# Placa_SecadorDeGraos_SL.net
KiCad netlist of a schematic drawn in EAGLE
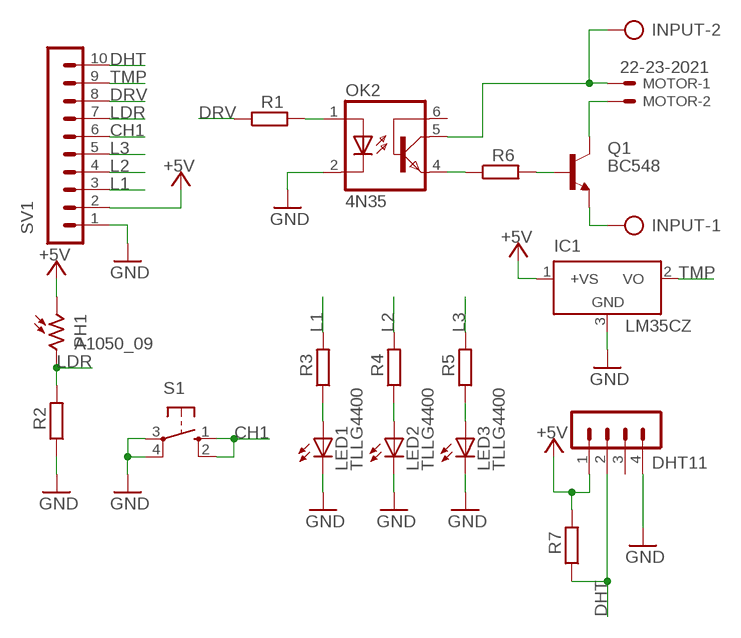
[diagram p0: schematic, sheet 1]

(export (version "E")
  (design (tool "Eeschema 10.0.6"))
  (components
    (comp (ref "DHT11")
      (value "MA04-1")
      (footprint "eagle-import:MA04-1")
      (libsource (lib "eagle-import") (part "MA04-1"))
    )
    (comp (ref "IC1")
      (value "LM35CZ")
      (footprint "eagle-import:TO92")
      (libsource (lib "eagle-import") (part "LM35CZ"))
    )
    (comp (ref "INPUT")
      (value "AK500/2")
      (footprint "eagle-import:AK500_2")
      (libsource (lib "eagle-import") (part "AK500/2"))
    )
    (comp (ref "LED1")
      (value "TLLG4400")
      (footprint "eagle-import:LED3MM")
      (fields (field (name "MF") "VISHAY SEMICONDUCTOR"))
      (libsource (lib "eagle-import") (part "TLLG4400"))
    )
    (comp (ref "LED2")
      (value "TLLG4400")
      (footprint "eagle-import:LED3MM")
      (fields (field (name "MF") "VISHAY SEMICONDUCTOR"))
      (libsource (lib "eagle-import") (part "TLLG4400"))
    )
    (comp (ref "LED3")
      (value "TLLG4400")
      (footprint "eagle-import:LED3MM")
      (fields (field (name "MF") "VISHAY SEMICONDUCTOR"))
      (libsource (lib "eagle-import") (part "TLLG4400"))
    )
    (comp (ref "MOTOR")
      (value "22-23-2021")
      (footprint "eagle-import:22-23-2021")
      (fields (field (name "MF") "MOLEX"))
      (libsource (lib "eagle-import") (part "22-23-2021"))
    )
    (comp (ref "OK2")
      (value "4N35")
      (footprint "eagle-import:DIL06")
      (fields (field (name "MF") "FAIRCHILD SEMICONDUCTOR"))
      (libsource (lib "eagle-import") (part "4N35"))
    )
    (comp (ref "PH1")
      (value "A1050_09")
      (footprint "eagle-import:T0-46-A10XX")
      (libsource (lib "eagle-import") (part "A1050_09"))
    )
    (comp (ref "Q1")
      (value "BC548")
      (footprint "eagle-import:TO92-EBC")
      (libsource (lib "eagle-import") (part "BC548"))
    )
    (comp (ref "R1")
      (value "R-EU_0204/7")
      (footprint "eagle-import:0204_7")
      (libsource (lib "eagle-import") (part "R-EU_0204/7"))
    )
    (comp (ref "R2")
      (value "R-EU_0204/7")
      (footprint "eagle-import:0204_7")
      (libsource (lib "eagle-import") (part "R-EU_0204/7"))
    )
    (comp (ref "R3")
      (value "R-EU_0204/7")
      (footprint "eagle-import:0204_7")
      (libsource (lib "eagle-import") (part "R-EU_0204/7"))
    )
    (comp (ref "R4")
      (value "R-EU_0204/7")
      (footprint "eagle-import:0204_7")
      (libsource (lib "eagle-import") (part "R-EU_0204/7"))
    )
    (comp (ref "R5")
      (value "R-EU_0204/7")
      (footprint "eagle-import:0204_7")
      (libsource (lib "eagle-import") (part "R-EU_0204/7"))
    )
    (comp (ref "R6")
      (value "R-EU_0204/7")
      (footprint "eagle-import:0204_7")
      (libsource (lib "eagle-import") (part "R-EU_0204/7"))
    )
    (comp (ref "R7")
      (value "R-EU_0204/7")
      (footprint "eagle-import:0204_7")
      (libsource (lib "eagle-import") (part "R-EU_0204/7"))
    )
    (comp (ref "S1")
      (value "10-XX")
      (footprint "eagle-import:B3F-10XX")
      (fields (field (name "MPN") "B3F-1000"))
      (libsource (lib "eagle-import") (part "10-XX"))
    )
    (comp (ref "SV1")
      (value "MA10-1")
      (footprint "eagle-import:MA10-1")
      (libsource (lib "eagle-import") (part "MA10-1"))
    )
  )
  (nets
    (net (code "1") (name "+5V") (class "Default")
      (node (ref "DHT11") (pin "1") (pinfunction "1_1") (pintype "passive"))
      (node (ref "IC1") (pin "1") (pinfunction "+VS_1") (pintype "input"))
      (node (ref "PH1") (pin "1") (pinfunction "1_1") (pintype "passive"))
      (node (ref "R7") (pin "2") (pinfunction "2_2") (pintype "passive"))
      (node (ref "SV1") (pin "2") (pinfunction "2_2") (pintype "passive"))
    )
    (net (code "2") (name "/CH1") (class "Default")
      (node (ref "S1") (pin "1") (pinfunction "S_1") (pintype "passive"))
      (node (ref "S1") (pin "2") (pinfunction "S1_2") (pintype "passive"))
      (node (ref "SV1") (pin "6") (pinfunction "6_6") (pintype "passive"))
    )
    (net (code "3") (name "/DHT") (class "Default")
      (node (ref "DHT11") (pin "2") (pinfunction "2_2") (pintype "passive"))
      (node (ref "R7") (pin "1") (pinfunction "1_1") (pintype "passive"))
      (node (ref "SV1") (pin "10") (pinfunction "10_10") (pintype "passive"))
    )
    (net (code "4") (name "/DRV") (class "Default")
      (node (ref "R1") (pin "1") (pinfunction "1_1") (pintype "passive"))
      (node (ref "SV1") (pin "8") (pinfunction "8_8") (pintype "passive"))
    )
    (net (code "5") (name "/L1") (class "Default")
      (node (ref "R3") (pin "2") (pinfunction "2_2") (pintype "passive"))
      (node (ref "SV1") (pin "3") (pinfunction "3_3") (pintype "passive"))
    )
    (net (code "6") (name "/L2") (class "Default")
      (node (ref "R4") (pin "2") (pinfunction "2_2") (pintype "passive"))
      (node (ref "SV1") (pin "4") (pinfunction "4_4") (pintype "passive"))
    )
    (net (code "7") (name "/L3") (class "Default")
      (node (ref "R5") (pin "2") (pinfunction "2_2") (pintype "passive"))
      (node (ref "SV1") (pin "5") (pinfunction "5_5") (pintype "passive"))
    )
    (net (code "8") (name "/LDR") (class "Default")
      (node (ref "PH1") (pin "2") (pinfunction "2_2") (pintype "passive"))
      (node (ref "R2") (pin "2") (pinfunction "2_2") (pintype "passive"))
      (node (ref "SV1") (pin "7") (pinfunction "7_7") (pintype "passive"))
    )
    (net (code "9") (name "/TMP") (class "Default")
      (node (ref "IC1") (pin "2") (pinfunction "VO_2") (pintype "input"))
      (node (ref "SV1") (pin "9") (pinfunction "9_9") (pintype "passive"))
    )
    (net (code "10") (name "GND") (class "Default")
      (node (ref "DHT11") (pin "4") (pinfunction "4_4") (pintype "passive"))
      (node (ref "IC1") (pin "3") (pinfunction "GND_3") (pintype "power_in"))
      (node (ref "LED1") (pin "K") (pinfunction "C_K") (pintype "passive"))
      (node (ref "LED2") (pin "K") (pinfunction "C_K") (pintype "passive"))
      (node (ref "LED3") (pin "K") (pinfunction "C_K") (pintype "passive"))
      (node (ref "OK2") (pin "2") (pinfunction "C_2") (pintype "passive"))
      (node (ref "R2") (pin "1") (pinfunction "1_1") (pintype "passive"))
      (node (ref "S1") (pin "3") (pinfunction "P_3") (pintype "passive"))
      (node (ref "S1") (pin "4") (pinfunction "P1_4") (pintype "passive"))
      (node (ref "SV1") (pin "1") (pinfunction "1_1") (pintype "passive"))
    )
    (net (code "11") (name "Net-(INPUTA-KL)") (class "Default")
      (node (ref "INPUT") (pin "1") (pinfunction "KL_1") (pintype "passive"))
      (node (ref "Q1") (pin "E") (pinfunction "E_E") (pintype "passive"))
    )
    (net (code "12") (name "Net-(INPUTB-KL)") (class "Default")
      (node (ref "INPUT") (pin "2") (pinfunction "KL_2") (pintype "passive"))
      (node (ref "MOTOR") (pin "1") (pinfunction "S_1") (pintype "passive"))
      (node (ref "OK2") (pin "5") (pinfunction "COL_5") (pintype "passive"))
    )
    (net (code "13") (name "Net-(LED1-PadA)") (class "Default")
      (node (ref "LED1") (pin "A") (pinfunction "A_A") (pintype "passive"))
      (node (ref "R3") (pin "1") (pinfunction "1_1") (pintype "passive"))
    )
    (net (code "14") (name "Net-(LED2-PadA)") (class "Default")
      (node (ref "LED2") (pin "A") (pinfunction "A_A") (pintype "passive"))
      (node (ref "R4") (pin "1") (pinfunction "1_1") (pintype "passive"))
    )
    (net (code "15") (name "Net-(LED3-PadA)") (class "Default")
      (node (ref "LED3") (pin "A") (pinfunction "A_A") (pintype "passive"))
      (node (ref "R5") (pin "1") (pinfunction "1_1") (pintype "passive"))
    )
    (net (code "16") (name "Net-(MOTORB-S)") (class "Default")
      (node (ref "MOTOR") (pin "2") (pinfunction "S_2") (pintype "passive"))
      (node (ref "Q1") (pin "C") (pinfunction "C_C") (pintype "passive"))
    )
    (net (code "17") (name "Net-(OK2-A)") (class "Default")
      (node (ref "OK2") (pin "1") (pinfunction "A_1") (pintype "passive"))
      (node (ref "R1") (pin "2") (pinfunction "2_2") (pintype "passive"))
    )
    (net (code "18") (name "Net-(OK2-EMI)") (class "Default")
      (node (ref "OK2") (pin "4") (pinfunction "EMI_4") (pintype "passive"))
      (node (ref "R6") (pin "1") (pinfunction "1_1") (pintype "passive"))
    )
    (net (code "19") (name "Net-(Q1-PadB)") (class "Default")
      (node (ref "Q1") (pin "B") (pinfunction "B_B") (pintype "passive"))
      (node (ref "R6") (pin "2") (pinfunction "2_2") (pintype "passive"))
    )
    (net (code "20") (name "unconnected-(DHT11-Pad3)") (class "Default")
      (node (ref "DHT11") (pin "3") (pinfunction "3_3") (pintype "passive"))
    )
    (net (code "21") (name "unconnected-(OK2-BAS-Pad6)") (class "Default")
      (node (ref "OK2") (pin "6") (pinfunction "BAS_6") (pintype "passive"))
    )
  )
)
